# NeoPixel_Stick.net
KiCad netlist of a schematic drawn in EAGLE
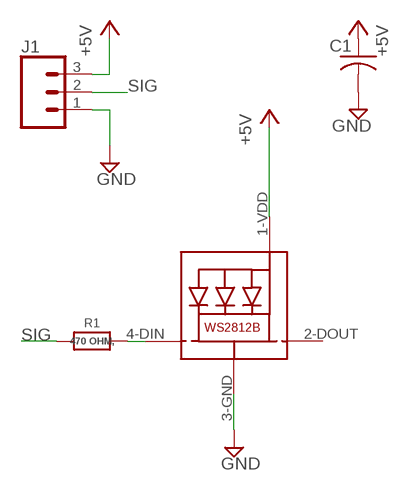
[diagram p0: schematic, sheet 1]

(export (version "E")
  (design (tool "Eeschema 10.0.6"))
  (components
    (comp (ref "C1")
      (value "C-USC0805K")
      (footprint "eagle-import:C0805K")
      (libsource (lib "eagle-import") (part "C-USC0805K"))
    )
    (comp (ref "J1")
      (value "CONN_03LONGPADS")
      (footprint "eagle-import:1X03_LONGPADS")
      (libsource (lib "eagle-import") (part "CONN_03LONGPADS"))
    )
    (comp (ref "LED1")
      (value "WS2812B5050")
      (footprint "eagle-import:WS2812B")
      (libsource (lib "eagle-import") (part "WS2812B5050"))
    )
    (comp (ref "R1")
      (value "470 OHM,")
      (footprint "eagle-import:_0805MP")
      (libsource (lib "eagle-import") (part "RESISTOR_0805MP"))
    )
  )
  (nets
    (net (code "1") (name "+5V") (class "Default")
      (node (ref "C1") (pin "1") (pinfunction "1_1") (pintype "passive"))
      (node (ref "J1") (pin "3") (pinfunction "3_3") (pintype "passive"))
      (node (ref "LED1") (pin "1-VDD") (pinfunction "VDD_1-VDD") (pintype "power_in"))
    )
    (net (code "2") (name "/SIG") (class "Default")
      (node (ref "J1") (pin "2") (pinfunction "2_2") (pintype "passive"))
      (node (ref "R1") (pin "1") (pinfunction "1_1") (pintype "passive"))
    )
    (net (code "3") (name "GND") (class "Default")
      (node (ref "C1") (pin "2") (pinfunction "2_2") (pintype "passive"))
      (node (ref "J1") (pin "1") (pinfunction "1_1") (pintype "passive"))
      (node (ref "LED1") (pin "3-GND") (pinfunction "GND_3-GND") (pintype "power_in"))
    )
    (net (code "4") (name "Net-(LED1-DI)") (class "Default")
      (node (ref "LED1") (pin "4-DIN") (pinfunction "DI_4-DIN") (pintype "input"))
      (node (ref "R1") (pin "2") (pinfunction "2_2") (pintype "passive"))
    )
    (net (code "5") (name "unconnected-(LED1-DO-Pad2-DOUT)") (class "Default")
      (node (ref "LED1") (pin "2-DOUT") (pinfunction "DO_2-DOUT") (pintype "output"))
    )
  )
)
